# SSB_Transceiver_Mic_Amplifier.net
KiCad netlist of a schematic drawn in EAGLE
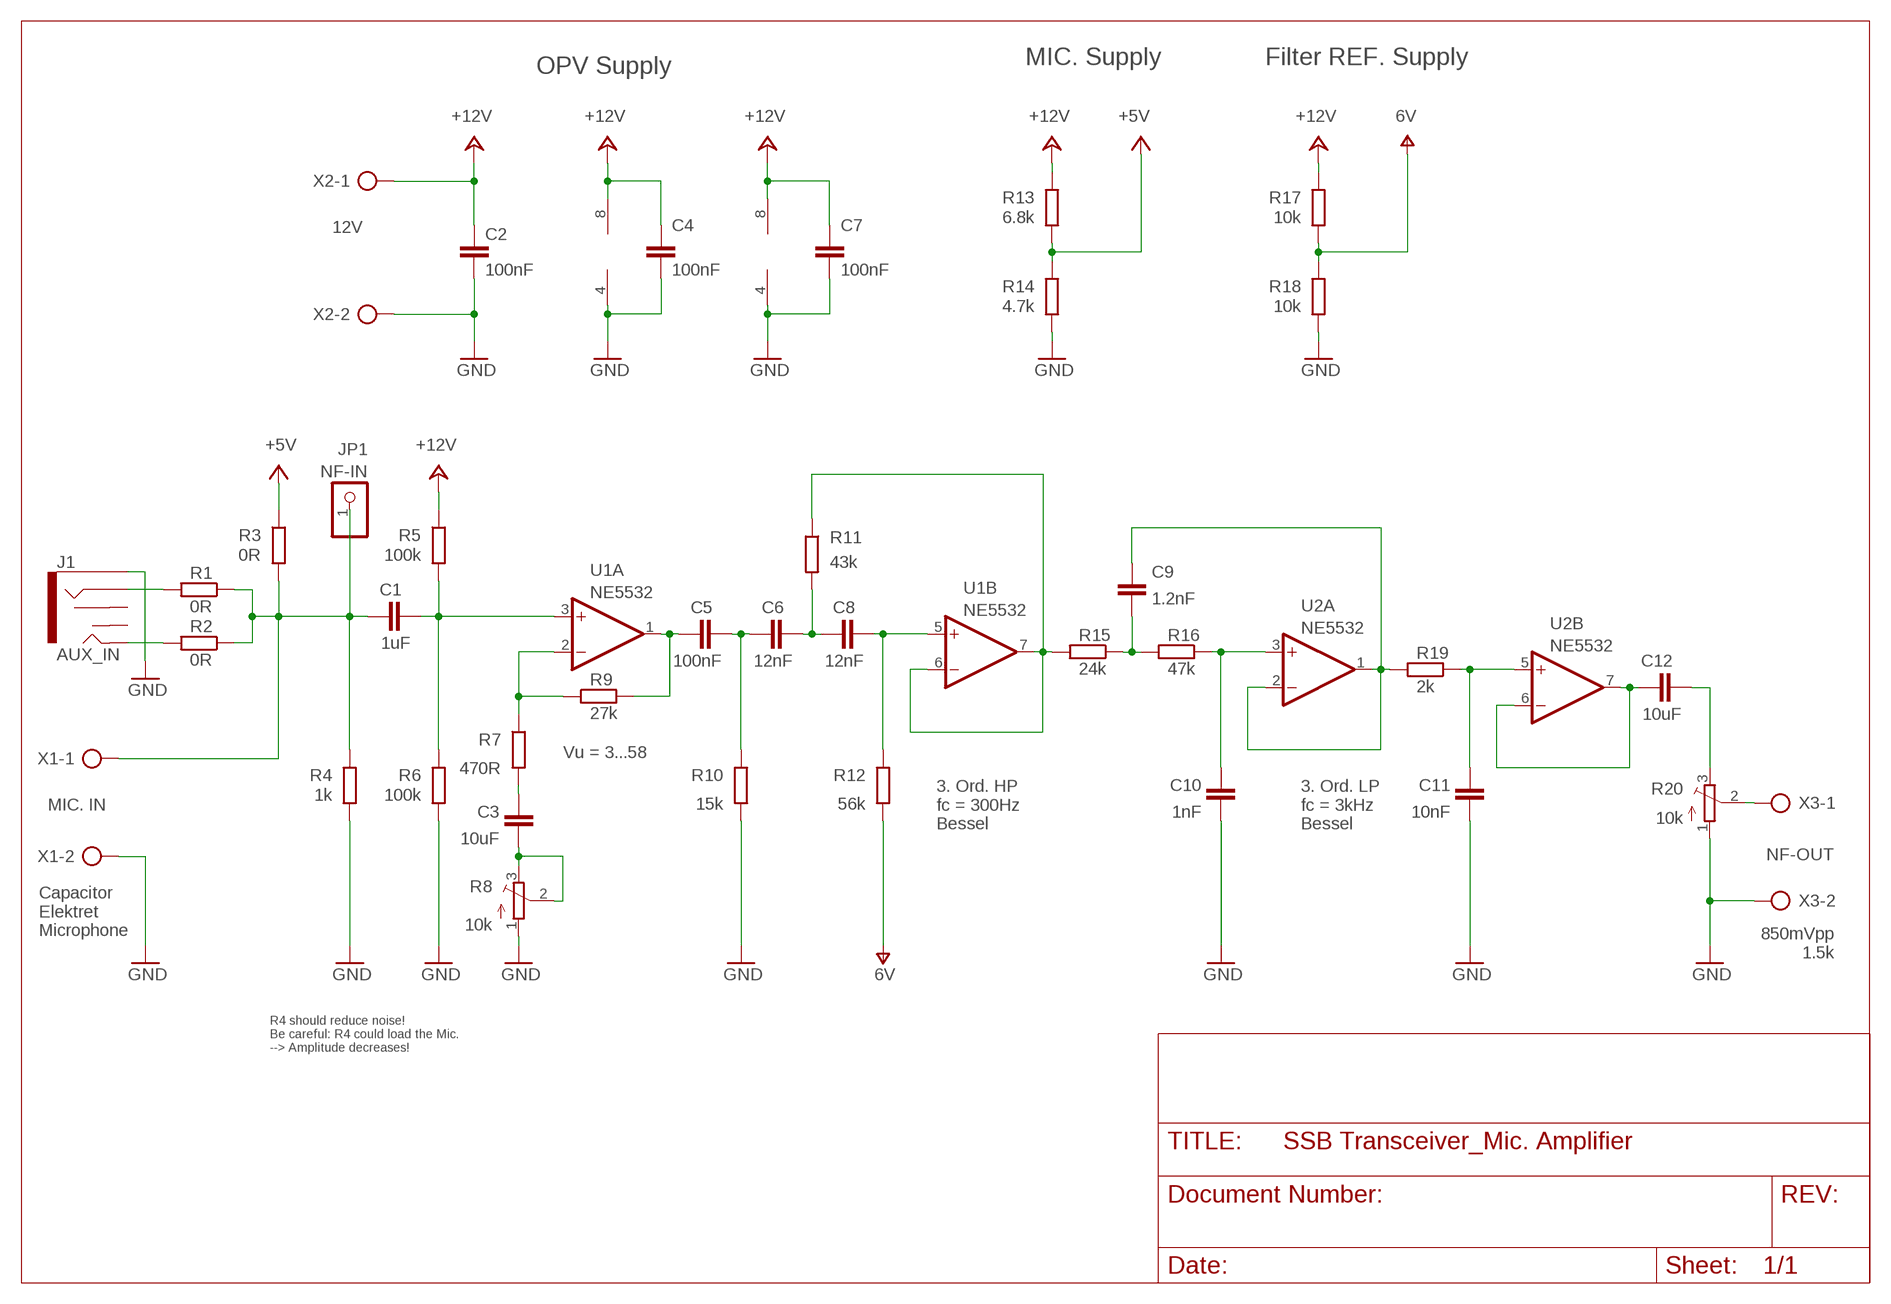
[diagram p0: schematic, sheet 1]

(export (version "E")
  (design (tool "Eeschema 10.0.6"))
  (components
    (comp (ref "C1")
      (value "1uF")
      (footprint "eagle-import:C0805")
      (libsource (lib "eagle-import") (part "C-EUC0805"))
    )
    (comp (ref "C2")
      (value "100nF")
      (footprint "eagle-import:C0805")
      (libsource (lib "eagle-import") (part "C-EUC0805"))
    )
    (comp (ref "C3")
      (value "10uF")
      (footprint "eagle-import:C0805")
      (libsource (lib "eagle-import") (part "C-EUC0805"))
    )
    (comp (ref "C4")
      (value "100nF")
      (footprint "eagle-import:C0805")
      (libsource (lib "eagle-import") (part "C-EUC0805"))
    )
    (comp (ref "C5")
      (value "100nF")
      (footprint "eagle-import:C0805")
      (libsource (lib "eagle-import") (part "C-EUC0805"))
    )
    (comp (ref "C6")
      (value "12nF")
      (footprint "eagle-import:C0805")
      (libsource (lib "eagle-import") (part "C-EUC0805"))
    )
    (comp (ref "C7")
      (value "100nF")
      (footprint "eagle-import:C0805")
      (libsource (lib "eagle-import") (part "C-EUC0805"))
    )
    (comp (ref "C8")
      (value "12nF")
      (footprint "eagle-import:C0805")
      (libsource (lib "eagle-import") (part "C-EUC0805"))
    )
    (comp (ref "C9")
      (value "1.2nF")
      (footprint "eagle-import:C0805")
      (libsource (lib "eagle-import") (part "C-EUC0805"))
    )
    (comp (ref "C10")
      (value "1nF")
      (footprint "eagle-import:C0805")
      (libsource (lib "eagle-import") (part "C-EUC0805"))
    )
    (comp (ref "C11")
      (value "10nF")
      (footprint "eagle-import:C0805")
      (libsource (lib "eagle-import") (part "C-EUC0805"))
    )
    (comp (ref "C12")
      (value "10uF")
      (footprint "eagle-import:C0805")
      (libsource (lib "eagle-import") (part "C-EUC0805"))
    )
    (comp (ref "J1")
      (value "AUX_IN")
      (footprint "eagle-import:AUDIO-JACK")
      (libsource (lib "eagle-import") (part "AUDIO_JACK_3.5MM_PTH"))
    )
    (comp (ref "JP1")
      (value "NF-IN")
      (footprint "eagle-import:1X01")
      (libsource (lib "eagle-import") (part "PINHD-1X1"))
    )
    (comp (ref "R1")
      (value "0R")
      (footprint "eagle-import:R0805")
      (libsource (lib "eagle-import") (part "R-EU_R0805"))
    )
    (comp (ref "R2")
      (value "0R")
      (footprint "eagle-import:R0805")
      (libsource (lib "eagle-import") (part "R-EU_R0805"))
    )
    (comp (ref "R3")
      (value "0R")
      (footprint "eagle-import:R0805")
      (libsource (lib "eagle-import") (part "R-EU_R0805"))
    )
    (comp (ref "R4")
      (value "1k")
      (footprint "eagle-import:R0805")
      (libsource (lib "eagle-import") (part "R-EU_R0805"))
    )
    (comp (ref "R5")
      (value "100k")
      (footprint "eagle-import:R0805")
      (libsource (lib "eagle-import") (part "R-EU_R0805"))
    )
    (comp (ref "R6")
      (value "100k")
      (footprint "eagle-import:R0805")
      (libsource (lib "eagle-import") (part "R-EU_R0805"))
    )
    (comp (ref "R7")
      (value "470R")
      (footprint "eagle-import:R0805")
      (libsource (lib "eagle-import") (part "R-EU_R0805"))
    )
    (comp (ref "R8")
      (value "10k")
      (footprint "eagle-import:3223G")
      (libsource (lib "eagle-import") (part "TRIM_EU-3223G"))
    )
    (comp (ref "R9")
      (value "27k")
      (footprint "eagle-import:R0805")
      (libsource (lib "eagle-import") (part "R-EU_R0805"))
    )
    (comp (ref "R10")
      (value "15k")
      (footprint "eagle-import:R0805")
      (libsource (lib "eagle-import") (part "R-EU_R0805"))
    )
    (comp (ref "R11")
      (value "43k")
      (footprint "eagle-import:R0805")
      (libsource (lib "eagle-import") (part "R-EU_R0805"))
    )
    (comp (ref "R12")
      (value "56k")
      (footprint "eagle-import:R0805")
      (libsource (lib "eagle-import") (part "R-EU_R0805"))
    )
    (comp (ref "R13")
      (value "6.8k")
      (footprint "eagle-import:R0805")
      (libsource (lib "eagle-import") (part "R-EU_R0805"))
    )
    (comp (ref "R14")
      (value "4.7k")
      (footprint "eagle-import:R0805")
      (libsource (lib "eagle-import") (part "R-EU_R0805"))
    )
    (comp (ref "R15")
      (value "24k")
      (footprint "eagle-import:R0805")
      (libsource (lib "eagle-import") (part "R-EU_R0805"))
    )
    (comp (ref "R16")
      (value "47k")
      (footprint "eagle-import:R0805")
      (libsource (lib "eagle-import") (part "R-EU_R0805"))
    )
    (comp (ref "R17")
      (value "10k")
      (footprint "eagle-import:R0805")
      (libsource (lib "eagle-import") (part "R-EU_R0805"))
    )
    (comp (ref "R18")
      (value "10k")
      (footprint "eagle-import:R0805")
      (libsource (lib "eagle-import") (part "R-EU_R0805"))
    )
    (comp (ref "R19")
      (value "2k")
      (footprint "eagle-import:R0805")
      (libsource (lib "eagle-import") (part "R-EU_R0805"))
    )
    (comp (ref "R20")
      (value "10k")
      (footprint "eagle-import:3223G")
      (libsource (lib "eagle-import") (part "TRIM_EU-3223G"))
    )
    (comp (ref "U1")
      (value "NE5532")
      (footprint "eagle-import:SO08")
      (libsource (lib "eagle-import") (part "TL072D"))
    )
    (comp (ref "U2")
      (value "NE5532")
      (footprint "eagle-import:SO08")
      (libsource (lib "eagle-import") (part "TL072D"))
    )
    (comp (ref "X1")
      (value "MIC. IN")
      (footprint "eagle-import:AK550_2")
      (libsource (lib "eagle-import") (part "AK550/2"))
    )
    (comp (ref "X2")
      (value "12V")
      (footprint "eagle-import:AK550_2")
      (libsource (lib "eagle-import") (part "AK550/2"))
    )
    (comp (ref "X3")
      (value "NF-OUT")
      (footprint "eagle-import:AK550_2")
      (libsource (lib "eagle-import") (part "AK550/2"))
    )
  )
  (nets
    (net (code "1") (name "+5V") (class "Default")
      (node (ref "R13") (pin "2") (pinfunction "2_2") (pintype "passive"))
      (node (ref "R14") (pin "1") (pinfunction "1_1") (pintype "passive"))
      (node (ref "R3") (pin "1") (pinfunction "1_1") (pintype "passive"))
    )
    (net (code "2") (name "+12V") (class "Default")
      (node (ref "C2") (pin "2") (pinfunction "2_2") (pintype "passive"))
      (node (ref "C4") (pin "2") (pinfunction "2_2") (pintype "passive"))
      (node (ref "C7") (pin "2") (pinfunction "2_2") (pintype "passive"))
      (node (ref "R13") (pin "1") (pinfunction "1_1") (pintype "passive"))
      (node (ref "R17") (pin "1") (pinfunction "1_1") (pintype "passive"))
      (node (ref "R5") (pin "1") (pinfunction "1_1") (pintype "passive"))
      (node (ref "U1") (pin "8") (pinfunction "V+_8") (pintype "power_in"))
      (node (ref "U2") (pin "8") (pinfunction "V+_8") (pintype "power_in"))
      (node (ref "X2") (pin "1") (pinfunction "KL_1") (pintype "passive"))
    )
    (net (code "3") (name "6V") (class "Default")
      (node (ref "R12") (pin "2") (pinfunction "2_2") (pintype "passive"))
      (node (ref "R17") (pin "2") (pinfunction "2_2") (pintype "passive"))
      (node (ref "R18") (pin "1") (pinfunction "1_1") (pintype "passive"))
    )
    (net (code "4") (name "GND") (class "Default")
      (node (ref "C10") (pin "1") (pinfunction "1_1") (pintype "passive"))
      (node (ref "C11") (pin "1") (pinfunction "1_1") (pintype "passive"))
      (node (ref "C2") (pin "1") (pinfunction "1_1") (pintype "passive"))
      (node (ref "C4") (pin "1") (pinfunction "1_1") (pintype "passive"))
      (node (ref "C7") (pin "1") (pinfunction "1_1") (pintype "passive"))
      (node (ref "J1") (pin "SLEEVE") (pinfunction "SLEEVE_SLEEVE") (pintype "bidirectional"))
      (node (ref "R10") (pin "2") (pinfunction "2_2") (pintype "passive"))
      (node (ref "R14") (pin "2") (pinfunction "2_2") (pintype "passive"))
      (node (ref "R18") (pin "2") (pinfunction "2_2") (pintype "passive"))
      (node (ref "R20") (pin "1") (pinfunction "A_1") (pintype "passive"))
      (node (ref "R4") (pin "2") (pinfunction "2_2") (pintype "passive"))
      (node (ref "R6") (pin "2") (pinfunction "2_2") (pintype "passive"))
      (node (ref "R8") (pin "1") (pinfunction "A_1") (pintype "passive"))
      (node (ref "U1") (pin "4") (pinfunction "V-_4") (pintype "power_in"))
      (node (ref "U2") (pin "4") (pinfunction "V-_4") (pintype "power_in"))
      (node (ref "X1") (pin "2") (pinfunction "KL_2") (pintype "passive"))
      (node (ref "X2") (pin "2") (pinfunction "KL_2") (pintype "passive"))
      (node (ref "X3") (pin "2") (pinfunction "KL_2") (pintype "passive"))
    )
    (net (code "5") (name "Net-(C3-Pad2)") (class "Default")
      (node (ref "C3") (pin "2") (pinfunction "2_2") (pintype "passive"))
      (node (ref "R7") (pin "2") (pinfunction "2_2") (pintype "passive"))
    )
    (net (code "6") (name "Net-(C5-Pad2)") (class "Default")
      (node (ref "C5") (pin "2") (pinfunction "2_2") (pintype "passive"))
      (node (ref "C6") (pin "1") (pinfunction "1_1") (pintype "passive"))
      (node (ref "R10") (pin "1") (pinfunction "1_1") (pintype "passive"))
    )
    (net (code "7") (name "Net-(C6-Pad2)") (class "Default")
      (node (ref "C6") (pin "2") (pinfunction "2_2") (pintype "passive"))
      (node (ref "C8") (pin "1") (pinfunction "1_1") (pintype "passive"))
      (node (ref "R11") (pin "2") (pinfunction "2_2") (pintype "passive"))
    )
    (net (code "8") (name "Net-(C9-Pad1)") (class "Default")
      (node (ref "C9") (pin "1") (pinfunction "1_1") (pintype "passive"))
      (node (ref "R15") (pin "1") (pinfunction "1_1") (pintype "passive"))
      (node (ref "R16") (pin "2") (pinfunction "2_2") (pintype "passive"))
    )
    (net (code "9") (name "Net-(J1-PadRING)") (class "Default")
      (node (ref "J1") (pin "RING") (pinfunction "RING_RING") (pintype "bidirectional"))
      (node (ref "R1") (pin "2") (pinfunction "2_2") (pintype "passive"))
    )
    (net (code "10") (name "Net-(J1-PadTIP)") (class "Default")
      (node (ref "J1") (pin "TIP") (pinfunction "TIP_TIP") (pintype "bidirectional"))
      (node (ref "R2") (pin "2") (pinfunction "2_2") (pintype "passive"))
    )
    (net (code "11") (name "Net-(R8-E)") (class "Default")
      (node (ref "C3") (pin "1") (pinfunction "1_1") (pintype "passive"))
      (node (ref "R8") (pin "2") (pinfunction "S_2") (pintype "passive"))
      (node (ref "R8") (pin "3") (pinfunction "E_3") (pintype "passive"))
    )
    (net (code "12") (name "Net-(R20-E)") (class "Default")
      (node (ref "C12") (pin "2") (pinfunction "2_2") (pintype "passive"))
      (node (ref "R20") (pin "3") (pinfunction "E_3") (pintype "passive"))
    )
    (net (code "13") (name "Net-(R20-S)") (class "Default")
      (node (ref "R20") (pin "2") (pinfunction "S_2") (pintype "passive"))
      (node (ref "X3") (pin "1") (pinfunction "KL_1") (pintype "passive"))
    )
    (net (code "14") (name "Net-(U1A-+IN)") (class "Default")
      (node (ref "C1") (pin "2") (pinfunction "2_2") (pintype "passive"))
      (node (ref "R5") (pin "2") (pinfunction "2_2") (pintype "passive"))
      (node (ref "R6") (pin "1") (pinfunction "1_1") (pintype "passive"))
      (node (ref "U1") (pin "3") (pinfunction "+IN_3") (pintype "input"))
    )
    (net (code "15") (name "Net-(U1A--IN)") (class "Default")
      (node (ref "R7") (pin "1") (pinfunction "1_1") (pintype "passive"))
      (node (ref "R9") (pin "1") (pinfunction "1_1") (pintype "passive"))
      (node (ref "U1") (pin "2") (pinfunction "-IN_2") (pintype "input"))
    )
    (net (code "16") (name "Net-(U1A-OUT)") (class "Default")
      (node (ref "C5") (pin "1") (pinfunction "1_1") (pintype "passive"))
      (node (ref "R9") (pin "2") (pinfunction "2_2") (pintype "passive"))
      (node (ref "U1") (pin "1") (pinfunction "OUT_1") (pintype "output"))
    )
    (net (code "17") (name "Net-(U1B-+IN)") (class "Default")
      (node (ref "C8") (pin "2") (pinfunction "2_2") (pintype "passive"))
      (node (ref "R12") (pin "1") (pinfunction "1_1") (pintype "passive"))
      (node (ref "U1") (pin "5") (pinfunction "+IN_5") (pintype "input"))
    )
    (net (code "18") (name "Net-(U1B--IN)") (class "Default")
      (node (ref "R11") (pin "1") (pinfunction "1_1") (pintype "passive"))
      (node (ref "R15") (pin "2") (pinfunction "2_2") (pintype "passive"))
      (node (ref "U1") (pin "6") (pinfunction "-IN_6") (pintype "input"))
      (node (ref "U1") (pin "7") (pinfunction "OUT_7") (pintype "output"))
    )
    (net (code "19") (name "Net-(U2A-+IN)") (class "Default")
      (node (ref "C10") (pin "2") (pinfunction "2_2") (pintype "passive"))
      (node (ref "R16") (pin "1") (pinfunction "1_1") (pintype "passive"))
      (node (ref "U2") (pin "3") (pinfunction "+IN_3") (pintype "input"))
    )
    (net (code "20") (name "Net-(U2A--IN)") (class "Default")
      (node (ref "C9") (pin "2") (pinfunction "2_2") (pintype "passive"))
      (node (ref "R19") (pin "2") (pinfunction "2_2") (pintype "passive"))
      (node (ref "U2") (pin "1") (pinfunction "OUT_1") (pintype "output"))
      (node (ref "U2") (pin "2") (pinfunction "-IN_2") (pintype "input"))
    )
    (net (code "21") (name "Net-(U2B-+IN)") (class "Default")
      (node (ref "C11") (pin "2") (pinfunction "2_2") (pintype "passive"))
      (node (ref "R19") (pin "1") (pinfunction "1_1") (pintype "passive"))
      (node (ref "U2") (pin "5") (pinfunction "+IN_5") (pintype "input"))
    )
    (net (code "22") (name "Net-(U2B--IN)") (class "Default")
      (node (ref "C12") (pin "1") (pinfunction "1_1") (pintype "passive"))
      (node (ref "U2") (pin "6") (pinfunction "-IN_6") (pintype "input"))
      (node (ref "U2") (pin "7") (pinfunction "OUT_7") (pintype "output"))
    )
    (net (code "23") (name "Net-(X1A-KL)") (class "Default")
      (node (ref "C1") (pin "1") (pinfunction "1_1") (pintype "passive"))
      (node (ref "JP1") (pin "1") (pinfunction "1_1") (pintype "passive"))
      (node (ref "R1") (pin "1") (pinfunction "1_1") (pintype "passive"))
      (node (ref "R2") (pin "1") (pinfunction "1_1") (pintype "passive"))
      (node (ref "R3") (pin "2") (pinfunction "2_2") (pintype "passive"))
      (node (ref "R4") (pin "1") (pinfunction "1_1") (pintype "passive"))
      (node (ref "X1") (pin "1") (pinfunction "KL_1") (pintype "passive"))
    )
    (net (code "24") (name "unconnected-(J1-PadRSH)") (class "Default")
      (node (ref "J1") (pin "RSH") (pinfunction "RSH_RSH") (pintype "bidirectional"))
    )
    (net (code "25") (name "unconnected-(J1-PadTSH)") (class "Default")
      (node (ref "J1") (pin "TSH") (pinfunction "TSH_TSH") (pintype "bidirectional"))
    )
  )
)
